# shema_projekt_kor4.net
KiCad netlist of a schematic drawn in Altium Designer
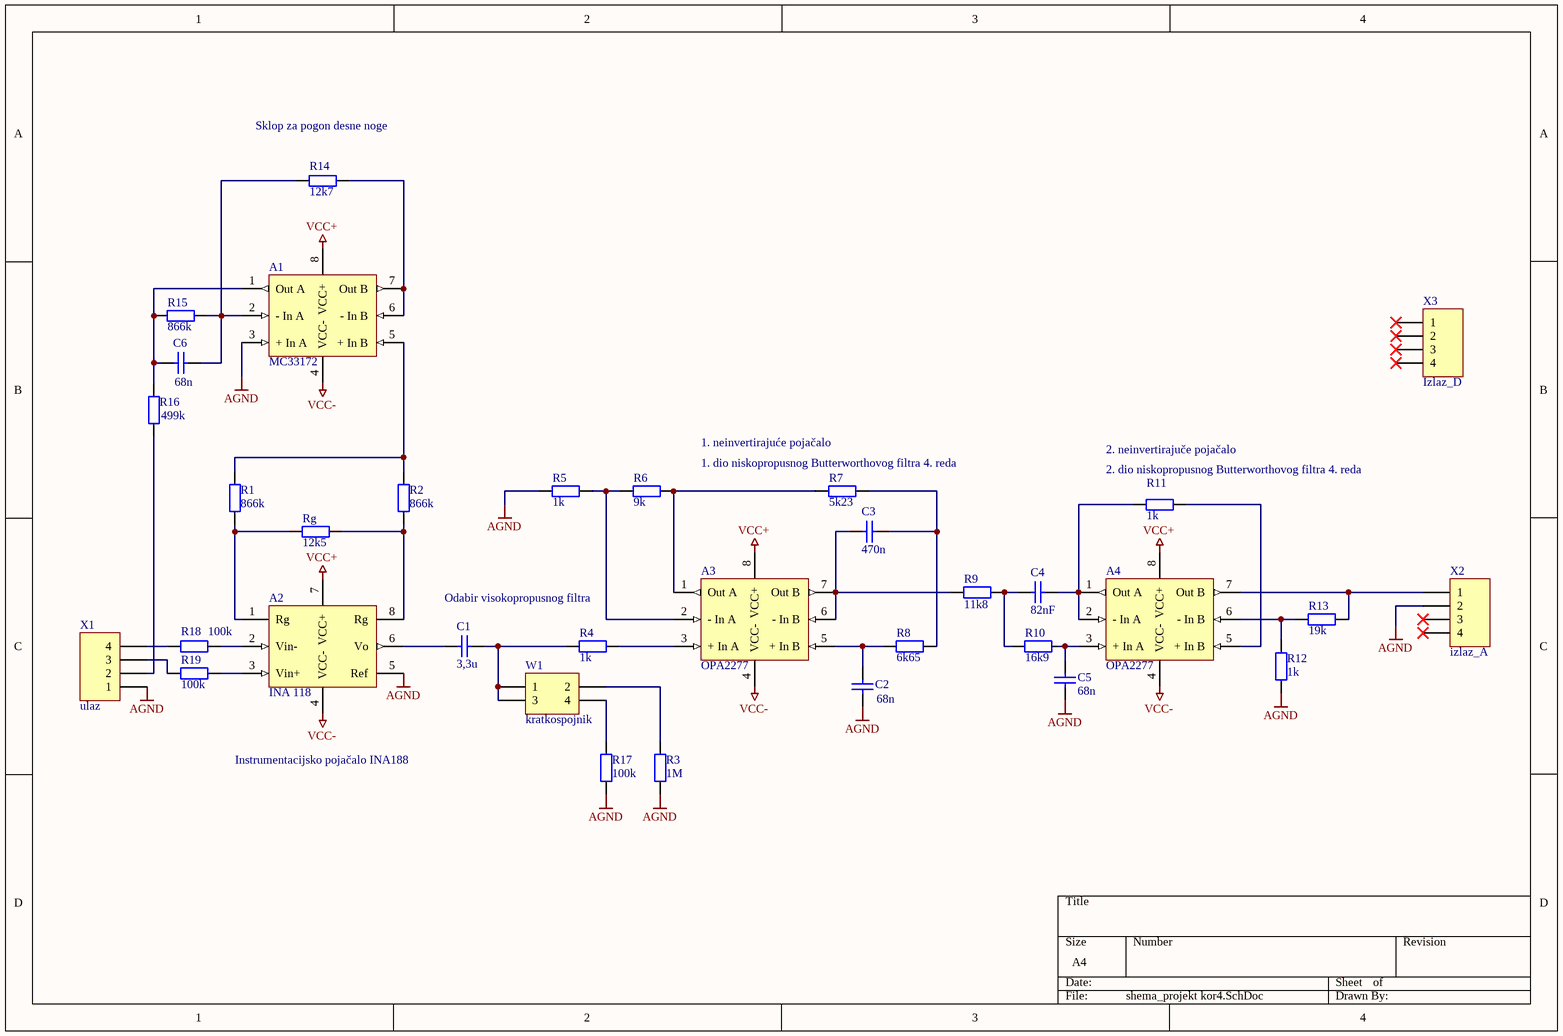
[diagram p0: shema_projekt kor4.SchDoc]

(export (version "E")
  (design (tool "Eeschema 10.0.6"))
  (components
    (comp (ref "A1")
      (value "MC33172")
      (footprint "SOIC127P600X175-8N")
      (libsource (lib "pojacala") (part "OPA2333"))
    )
    (comp (ref "A2")
      (value "INA 118")
      (footprint "SOIC127P600X175-8N")
      (libsource (lib "pojacala") (part "INA 333"))
    )
    (comp (ref "A3")
      (value "OPA2277")
      (footprint "SOIC127P600X175-8N")
      (libsource (lib "pojacala") (part "OPA2277"))
    )
    (comp (ref "A4")
      (value "OPA2277")
      (footprint "SOIC127P600X175-8N")
      (libsource (lib "pojacala") (part "OPA2277"))
    )
    (comp (ref "C1")
      (value "3,3u")
      (footprint "C0805")
      (description "Capacitor")
      (fields (field (name "PUBLISHER") "Altium Limited"))
      (libsource (lib "Miscellaneous Devices") (part "Cap"))
    )
    (comp (ref "C2")
      (value "68n")
      (footprint "C0805")
      (description "Capacitor")
      (fields (field (name "PUBLISHER") "Altium Limited"))
      (libsource (lib "Miscellaneous Devices") (part "Cap"))
    )
    (comp (ref "C3")
      (value "470n")
      (footprint "C0805")
      (description "Capacitor")
      (fields (field (name "PUBLISHER") "Altium Limited"))
      (libsource (lib "Miscellaneous Devices") (part "Cap"))
    )
    (comp (ref "C4")
      (value "82nF")
      (footprint "C0805")
      (description "Capacitor")
      (fields (field (name "PUBLISHER") "Altium Limited"))
      (libsource (lib "Miscellaneous Devices") (part "Cap"))
    )
    (comp (ref "C5")
      (value "68n")
      (footprint "C0805")
      (description "Capacitor")
      (fields (field (name "PUBLISHER") "Altium Limited"))
      (libsource (lib "Miscellaneous Devices") (part "Cap"))
    )
    (comp (ref "C6")
      (value "68n")
      (footprint "C0805")
      (description "Capacitor")
      (fields (field (name "PUBLISHER") "Altium Limited"))
      (libsource (lib "Miscellaneous Devices") (part "Cap"))
    )
    (comp (ref "R1")
      (value "866k")
      (footprint "C0805")
      (description "Resistor")
      (fields (field (name "PUBLISHER") "Altium Limited"))
      (libsource (lib "") (part "Res2_1"))
    )
    (comp (ref "R2")
      (value "866k")
      (footprint "C0805")
      (description "Resistor")
      (fields (field (name "PUBLISHER") "Altium Limited"))
      (libsource (lib "") (part "Res2_2"))
    )
    (comp (ref "R3")
      (value "1M")
      (footprint "C0805")
      (description "Resistor")
      (fields (field (name "PUBLISHER") "Altium Limited"))
      (libsource (lib "") (part "Res2_1"))
    )
    (comp (ref "R4")
      (value "1k")
      (footprint "C0805")
      (description "Resistor")
      (fields (field (name "PUBLISHER") "Altium Limited"))
      (libsource (lib "Miscellaneous Devices") (part "Res2"))
    )
    (comp (ref "R5")
      (value "1k")
      (footprint "C0805")
      (description "Resistor")
      (fields (field (name "PUBLISHER") "Altium Limited"))
      (libsource (lib "Miscellaneous Devices") (part "Res2"))
    )
    (comp (ref "R6")
      (value "9k")
      (footprint "C0805")
      (description "Resistor")
      (fields (field (name "PUBLISHER") "Altium Limited"))
      (libsource (lib "Miscellaneous Devices") (part "Res2"))
    )
    (comp (ref "R7")
      (value "5k23")
      (footprint "C0805")
      (description "Resistor")
      (fields (field (name "PUBLISHER") "Altium Limited"))
      (libsource (lib "Miscellaneous Devices") (part "Res2"))
    )
    (comp (ref "R8")
      (value "6k65")
      (footprint "C0805")
      (description "Resistor")
      (fields (field (name "PUBLISHER") "Altium Limited"))
      (libsource (lib "Miscellaneous Devices") (part "Res2"))
    )
    (comp (ref "R9")
      (value "11k8")
      (footprint "C0805")
      (description "Resistor")
      (fields (field (name "PUBLISHER") "Altium Limited"))
      (libsource (lib "") (part "Res2_3"))
    )
    (comp (ref "R10")
      (value "16k9")
      (footprint "C0805")
      (description "Resistor")
      (fields (field (name "PUBLISHER") "Altium Limited"))
      (libsource (lib "Miscellaneous Devices") (part "Res2"))
    )
    (comp (ref "R11")
      (value "1k")
      (footprint "C0805")
      (description "Resistor")
      (fields (field (name "PUBLISHER") "Altium Limited"))
      (libsource (lib "Miscellaneous Devices") (part "Res2"))
    )
    (comp (ref "R12")
      (value "1k")
      (footprint "C0805")
      (description "Resistor")
      (fields (field (name "PUBLISHER") "Altium Limited"))
      (libsource (lib "") (part "Res2_1"))
    )
    (comp (ref "R13")
      (value "19k")
      (footprint "C0805")
      (description "Resistor")
      (fields (field (name "PUBLISHER") "Altium Limited"))
      (libsource (lib "Miscellaneous Devices") (part "Res2"))
    )
    (comp (ref "R14")
      (value "12k7")
      (footprint "C0805")
      (description "Resistor")
      (fields (field (name "PUBLISHER") "Altium Limited"))
      (libsource (lib "Miscellaneous Devices") (part "Res2"))
    )
    (comp (ref "R15")
      (value "866k")
      (footprint "C0805")
      (description "Resistor")
      (fields (field (name "PUBLISHER") "Altium Limited"))
      (libsource (lib "Miscellaneous Devices") (part "Res2"))
    )
    (comp (ref "R16")
      (value "499k")
      (footprint "C0805")
      (description "Resistor")
      (fields (field (name "PUBLISHER") "Altium Limited"))
      (libsource (lib "") (part "Res2_1"))
    )
    (comp (ref "R17")
      (value "100k")
      (footprint "C0805")
      (description "Resistor")
      (fields (field (name "PUBLISHER") "Altium Limited"))
      (libsource (lib "") (part "Res2_1"))
    )
    (comp (ref "R18")
      (value "100k")
      (footprint "C0805")
      (description "Resistor")
      (fields (field (name "PUBLISHER") "Altium Limited"))
      (libsource (lib "") (part "Res2_3"))
    )
    (comp (ref "R19")
      (value "100k")
      (footprint "C0805")
      (description "Resistor")
      (fields (field (name "PUBLISHER") "Altium Limited"))
      (libsource (lib "Miscellaneous Devices") (part "Res2"))
    )
    (comp (ref "Rg")
      (value "12k5")
      (footprint "C0805")
      (description "Resistor")
      (fields (field (name "PUBLISHER") "Altium Limited"))
      (libsource (lib "Miscellaneous Devices") (part "Res2"))
    )
    (comp (ref "W1")
      (value "kratkospojnik")
      (footprint "HDR2X2")
      (description "Header, 2-Pin, Dual row")
      (fields (field (name "PUBLISHER") "Altium Limited"))
      (libsource (lib "Miscellaneous Connectors") (part "Header 2X2"))
    )
    (comp (ref "X1")
      (value "ulaz")
      (footprint "HDR1X4")
      (description "Header, 4-Pin, Right Angle")
      (fields (field (name "PUBLISHER") "Altium Limited"))
      (libsource (lib "") (part "Header 4H_1"))
    )
    (comp (ref "X2")
      (value "izlaz_A")
      (footprint "HDR1X4")
      (description "Header, 4-Pin, Right Angle")
      (fields (field (name "PUBLISHER") "Altium Limited"))
      (libsource (lib "Miscellaneous Connectors") (part "Header 4H"))
    )
    (comp (ref "X3")
      (value "Izlaz_D")
      (footprint "HDR1X4")
      (description "Header, 4-Pin, Right Angle")
      (fields (field (name "PUBLISHER") "Altium Limited"))
      (libsource (lib "Miscellaneous Connectors") (part "Header 4H"))
    )
  )
  (nets
    (net (code "1") (name "AGND") (class "Default")
      (node (ref "A1") (pin "3") (pinfunction "+_In_A_3") (pintype "input"))
      (node (ref "A2") (pin "5") (pinfunction "Ref_5") (pintype "passive"))
      (node (ref "C2") (pin "2") (pinfunction "2_2") (pintype "passive"))
      (node (ref "C5") (pin "2") (pinfunction "2_2") (pintype "passive"))
      (node (ref "R12") (pin "2") (pinfunction "2_2") (pintype "passive"))
      (node (ref "R17") (pin "2") (pinfunction "2_2") (pintype "passive"))
      (node (ref "R3") (pin "2") (pinfunction "2_2") (pintype "passive"))
      (node (ref "R5") (pin "1") (pinfunction "1_1") (pintype "passive"))
      (node (ref "X1") (pin "1") (pinfunction "1_1") (pintype "passive"))
      (node (ref "X2") (pin "2") (pinfunction "2_2") (pintype "passive"))
    )
    (net (code "2") (name "Net-(A1-+_In_B)") (class "Default")
      (node (ref "A1") (pin "5") (pinfunction "+_In_B_5") (pintype "input"))
      (node (ref "R1") (pin "1") (pinfunction "1_1") (pintype "passive"))
      (node (ref "R2") (pin "2") (pinfunction "2_2") (pintype "passive"))
    )
    (net (code "3") (name "Net-(A1--_In_A)") (class "Default")
      (node (ref "A1") (pin "2") (pinfunction "-_In_A_2") (pintype "input"))
      (node (ref "C6") (pin "2") (pinfunction "2_2") (pintype "passive"))
      (node (ref "R14") (pin "1") (pinfunction "1_1") (pintype "passive"))
      (node (ref "R15") (pin "2") (pinfunction "2_2") (pintype "passive"))
    )
    (net (code "4") (name "Net-(A1--_In_B)") (class "Default")
      (node (ref "A1") (pin "6") (pinfunction "-_In_B_6") (pintype "input"))
      (node (ref "A1") (pin "7") (pinfunction "Out_B_7") (pintype "output"))
      (node (ref "R14") (pin "2") (pinfunction "2_2") (pintype "passive"))
    )
    (net (code "5") (name "Net-(A1-Out_A)") (class "Default")
      (node (ref "A1") (pin "1") (pinfunction "Out_A_1") (pintype "output"))
      (node (ref "C6") (pin "1") (pinfunction "1_1") (pintype "passive"))
      (node (ref "R15") (pin "1") (pinfunction "1_1") (pintype "passive"))
      (node (ref "R16") (pin "1") (pinfunction "1_1") (pintype "passive"))
    )
    (net (code "6") (name "Net-(A2-Rg-Pad1)") (class "Default")
      (node (ref "A2") (pin "1") (pinfunction "Rg_1") (pintype "passive"))
      (node (ref "R1") (pin "2") (pinfunction "2_2") (pintype "passive"))
      (node (ref "Rg") (pin "1") (pinfunction "1_1") (pintype "passive"))
    )
    (net (code "7") (name "Net-(A2-Rg-Pad8)") (class "Default")
      (node (ref "A2") (pin "8") (pinfunction "Rg_8") (pintype "passive"))
      (node (ref "R2") (pin "1") (pinfunction "1_1") (pintype "passive"))
      (node (ref "Rg") (pin "2") (pinfunction "2_2") (pintype "passive"))
    )
    (net (code "8") (name "Net-(A2-Vin+)") (class "Default")
      (node (ref "A2") (pin "3") (pinfunction "Vin+_3") (pintype "input"))
      (node (ref "R19") (pin "2") (pinfunction "2_2") (pintype "passive"))
    )
    (net (code "9") (name "Net-(A2-Vin-)") (class "Default")
      (node (ref "A2") (pin "2") (pinfunction "Vin-_2") (pintype "input"))
      (node (ref "R18") (pin "1") (pinfunction "1_1") (pintype "passive"))
    )
    (net (code "10") (name "Net-(A2-Vo)") (class "Default")
      (node (ref "A2") (pin "6") (pinfunction "Vo_6") (pintype "output"))
      (node (ref "C1") (pin "1") (pinfunction "1_1") (pintype "passive"))
    )
    (net (code "11") (name "Net-(A3-+_In_A)") (class "Default")
      (node (ref "A3") (pin "3") (pinfunction "+_In_A_3") (pintype "input"))
      (node (ref "R4") (pin "2") (pinfunction "2_2") (pintype "passive"))
    )
    (net (code "12") (name "Net-(A3-+_In_B)") (class "Default")
      (node (ref "A3") (pin "5") (pinfunction "+_In_B_5") (pintype "input"))
      (node (ref "C2") (pin "1") (pinfunction "1_1") (pintype "passive"))
      (node (ref "R8") (pin "1") (pinfunction "1_1") (pintype "passive"))
    )
    (net (code "13") (name "Net-(A3--_In_A)") (class "Default")
      (node (ref "A3") (pin "2") (pinfunction "-_In_A_2") (pintype "input"))
      (node (ref "R5") (pin "2") (pinfunction "2_2") (pintype "passive"))
      (node (ref "R6") (pin "1") (pinfunction "1_1") (pintype "passive"))
    )
    (net (code "14") (name "Net-(A3--_In_B)") (class "Default")
      (node (ref "A3") (pin "6") (pinfunction "-_In_B_6") (pintype "input"))
      (node (ref "A3") (pin "7") (pinfunction "Out_B_7") (pintype "output"))
      (node (ref "C3") (pin "1") (pinfunction "1_1") (pintype "passive"))
      (node (ref "R9") (pin "2") (pinfunction "2_2") (pintype "passive"))
    )
    (net (code "15") (name "Net-(A3-Out_A)") (class "Default")
      (node (ref "A3") (pin "1") (pinfunction "Out_A_1") (pintype "output"))
      (node (ref "R6") (pin "2") (pinfunction "2_2") (pintype "passive"))
      (node (ref "R7") (pin "1") (pinfunction "1_1") (pintype "passive"))
    )
    (net (code "16") (name "Net-(A4-+_In_A)") (class "Default")
      (node (ref "A4") (pin "3") (pinfunction "+_In_A_3") (pintype "input"))
      (node (ref "C5") (pin "1") (pinfunction "1_1") (pintype "passive"))
      (node (ref "R10") (pin "2") (pinfunction "2_2") (pintype "passive"))
    )
    (net (code "17") (name "Net-(A4-+_In_B)") (class "Default")
      (node (ref "A4") (pin "5") (pinfunction "+_In_B_5") (pintype "input"))
      (node (ref "R11") (pin "2") (pinfunction "2_2") (pintype "passive"))
    )
    (net (code "18") (name "Net-(A4--_In_A)") (class "Default")
      (node (ref "A4") (pin "1") (pinfunction "Out_A_1") (pintype "output"))
      (node (ref "A4") (pin "2") (pinfunction "-_In_A_2") (pintype "input"))
      (node (ref "C4") (pin "2") (pinfunction "2_2") (pintype "passive"))
      (node (ref "R11") (pin "1") (pinfunction "1_1") (pintype "passive"))
    )
    (net (code "19") (name "Net-(A4--_In_B)") (class "Default")
      (node (ref "A4") (pin "6") (pinfunction "-_In_B_6") (pintype "input"))
      (node (ref "R12") (pin "1") (pinfunction "1_1") (pintype "passive"))
      (node (ref "R13") (pin "1") (pinfunction "1_1") (pintype "passive"))
    )
    (net (code "20") (name "Net-(A4-Out_B)") (class "Default")
      (node (ref "A4") (pin "7") (pinfunction "Out_B_7") (pintype "output"))
      (node (ref "R13") (pin "2") (pinfunction "2_2") (pintype "passive"))
      (node (ref "X2") (pin "1") (pinfunction "1_1") (pintype "passive"))
    )
    (net (code "21") (name "Net-(C1-Pad2)") (class "Default")
      (node (ref "C1") (pin "2") (pinfunction "2_2") (pintype "passive"))
      (node (ref "R4") (pin "1") (pinfunction "1_1") (pintype "passive"))
      (node (ref "W1") (pin "1") (pinfunction "1_1") (pintype "passive"))
      (node (ref "W1") (pin "3") (pinfunction "3_3") (pintype "passive"))
    )
    (net (code "22") (name "Net-(C3-Pad2)") (class "Default")
      (node (ref "C3") (pin "2") (pinfunction "2_2") (pintype "passive"))
      (node (ref "R7") (pin "2") (pinfunction "2_2") (pintype "passive"))
      (node (ref "R8") (pin "2") (pinfunction "2_2") (pintype "passive"))
    )
    (net (code "23") (name "Net-(C4-Pad1)") (class "Default")
      (node (ref "C4") (pin "1") (pinfunction "1_1") (pintype "passive"))
      (node (ref "R10") (pin "1") (pinfunction "1_1") (pintype "passive"))
      (node (ref "R9") (pin "1") (pinfunction "1_1") (pintype "passive"))
    )
    (net (code "24") (name "Net-(R3-Pad1)") (class "Default")
      (node (ref "R3") (pin "1") (pinfunction "1_1") (pintype "passive"))
      (node (ref "W1") (pin "2") (pinfunction "2_2") (pintype "passive"))
    )
    (net (code "25") (name "Net-(R16-Pad2)") (class "Default")
      (node (ref "R16") (pin "2") (pinfunction "2_2") (pintype "passive"))
      (node (ref "X1") (pin "2") (pinfunction "2_2") (pintype "passive"))
    )
    (net (code "26") (name "Net-(R17-Pad1)") (class "Default")
      (node (ref "R17") (pin "1") (pinfunction "1_1") (pintype "passive"))
      (node (ref "W1") (pin "4") (pinfunction "4_4") (pintype "passive"))
    )
    (net (code "27") (name "Net-(R18-Pad2)") (class "Default")
      (node (ref "R18") (pin "2") (pinfunction "2_2") (pintype "passive"))
      (node (ref "X1") (pin "4") (pinfunction "4_4") (pintype "passive"))
    )
    (net (code "28") (name "Net-(R19-Pad1)") (class "Default")
      (node (ref "R19") (pin "1") (pinfunction "1_1") (pintype "passive"))
      (node (ref "X1") (pin "3") (pinfunction "3_3") (pintype "passive"))
    )
    (net (code "29") (name "VCC+") (class "Default")
      (node (ref "A1") (pin "8") (pinfunction "VCC+_8") (pintype "power_in"))
      (node (ref "A2") (pin "7") (pinfunction "VCC+_7") (pintype "power_in"))
      (node (ref "A3") (pin "8") (pinfunction "VCC+_8") (pintype "power_in"))
      (node (ref "A4") (pin "8") (pinfunction "VCC+_8") (pintype "power_in"))
    )
    (net (code "30") (name "VCC-") (class "Default")
      (node (ref "A1") (pin "4") (pinfunction "VCC-_4") (pintype "power_in"))
      (node (ref "A2") (pin "4") (pinfunction "VCC-_4") (pintype "power_in"))
      (node (ref "A3") (pin "4") (pinfunction "VCC-_4") (pintype "power_in"))
      (node (ref "A4") (pin "4") (pinfunction "VCC-_4") (pintype "power_in"))
    )
    (net (code "31") (name "unconnected-(X2-Pad3)") (class "Default")
      (node (ref "X2") (pin "3") (pinfunction "3_3") (pintype "passive+no_connect"))
    )
    (net (code "32") (name "unconnected-(X2-Pad4)") (class "Default")
      (node (ref "X2") (pin "4") (pinfunction "4_4") (pintype "passive+no_connect"))
    )
    (net (code "33") (name "unconnected-(X3-Pad1)") (class "Default")
      (node (ref "X3") (pin "1") (pinfunction "1_1") (pintype "passive+no_connect"))
    )
    (net (code "34") (name "unconnected-(X3-Pad2)") (class "Default")
      (node (ref "X3") (pin "2") (pinfunction "2_2") (pintype "passive+no_connect"))
    )
    (net (code "35") (name "unconnected-(X3-Pad3)") (class "Default")
      (node (ref "X3") (pin "3") (pinfunction "3_3") (pintype "passive+no_connect"))
    )
    (net (code "36") (name "unconnected-(X3-Pad4)") (class "Default")
      (node (ref "X3") (pin "4") (pinfunction "4_4") (pintype "passive+no_connect"))
    )
  )
)
